# smartstand-usb-dac-i2s-rev-a.net
KiCad netlist of a schematic drawn in EAGLE
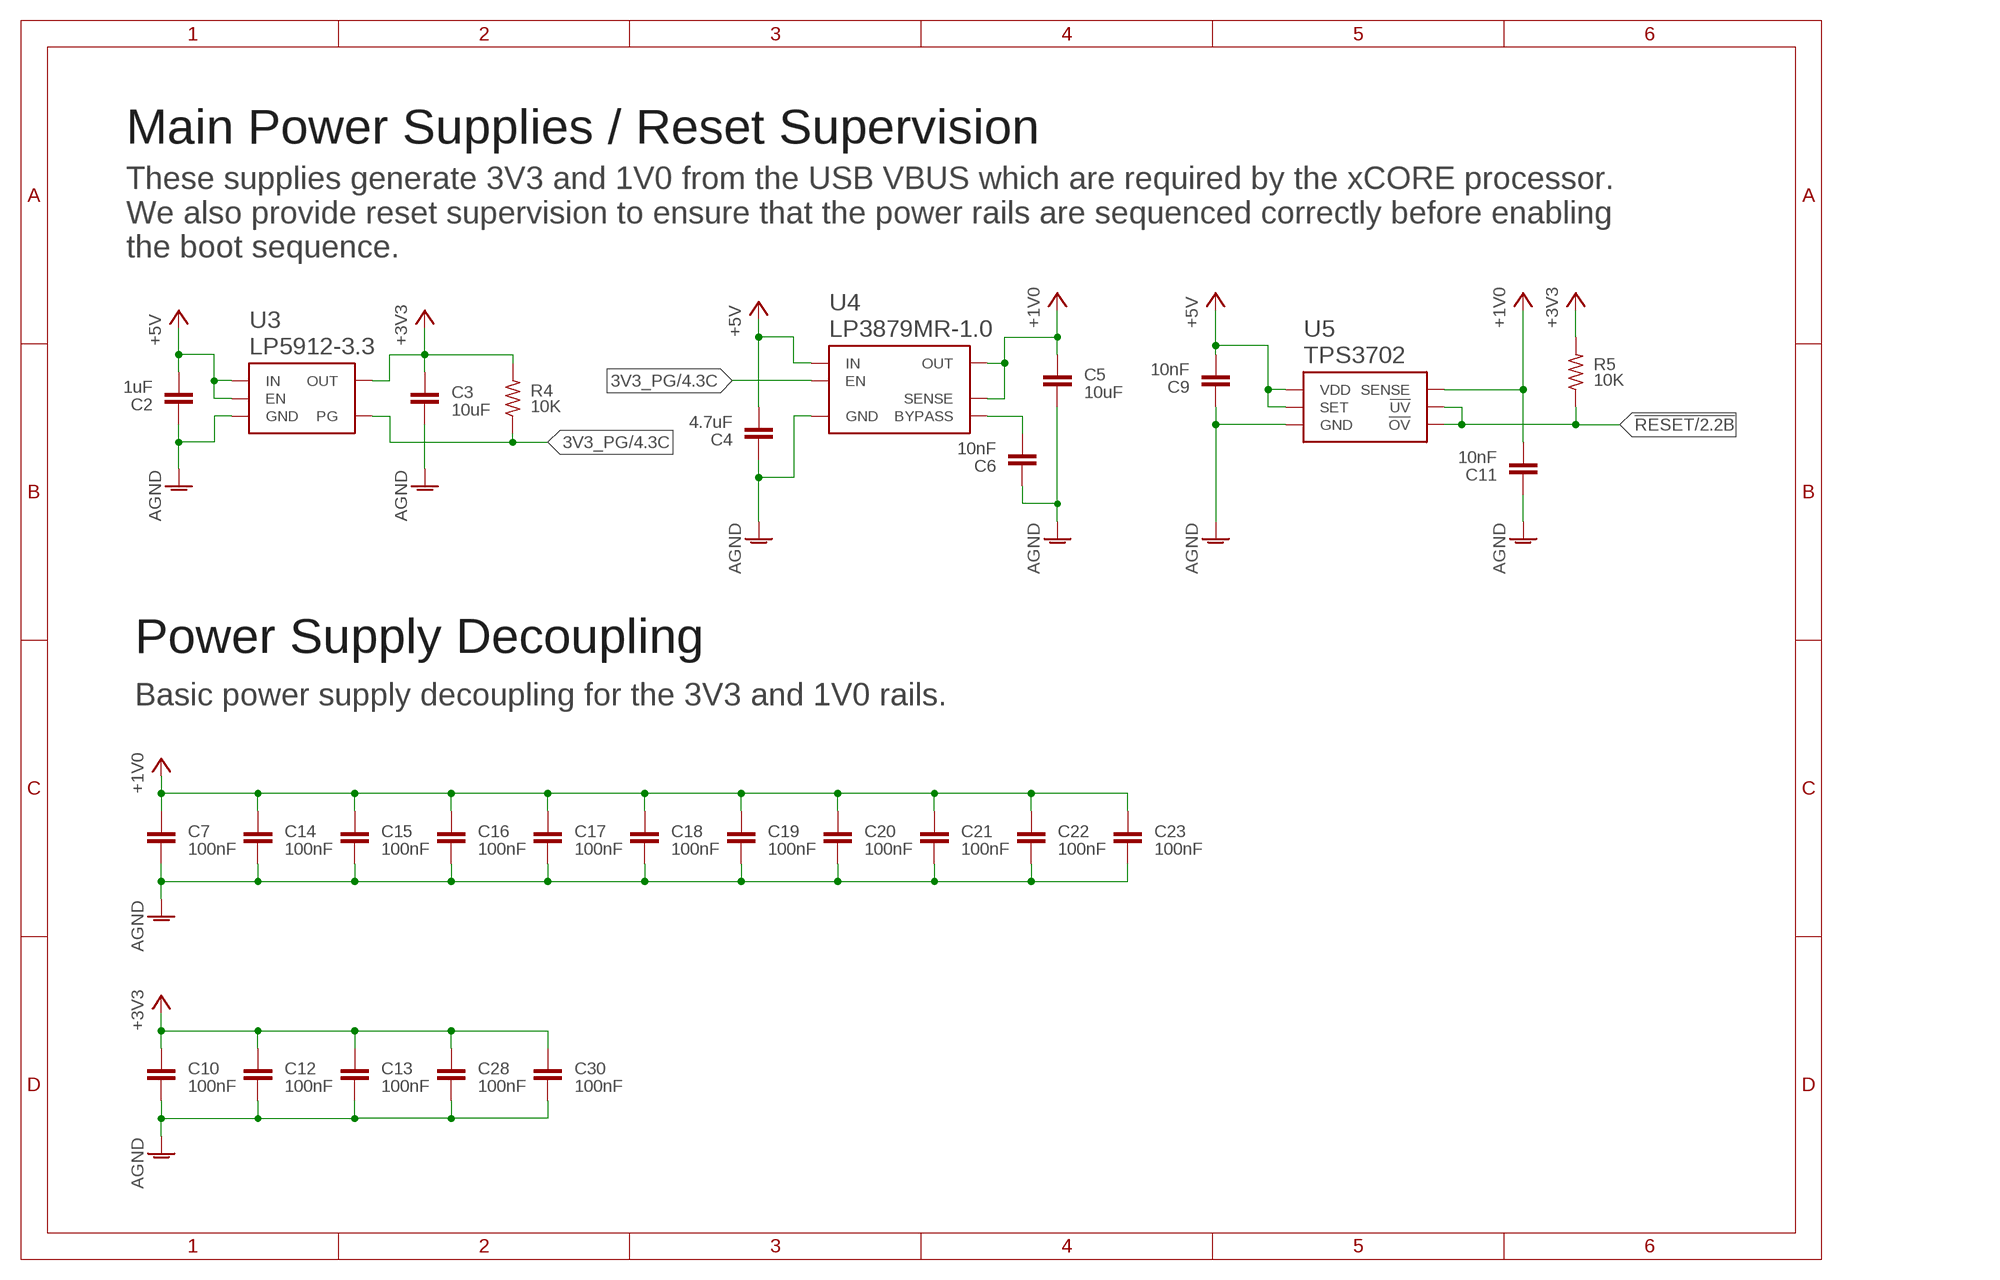
[diagram p0: schematic, sheet 1]
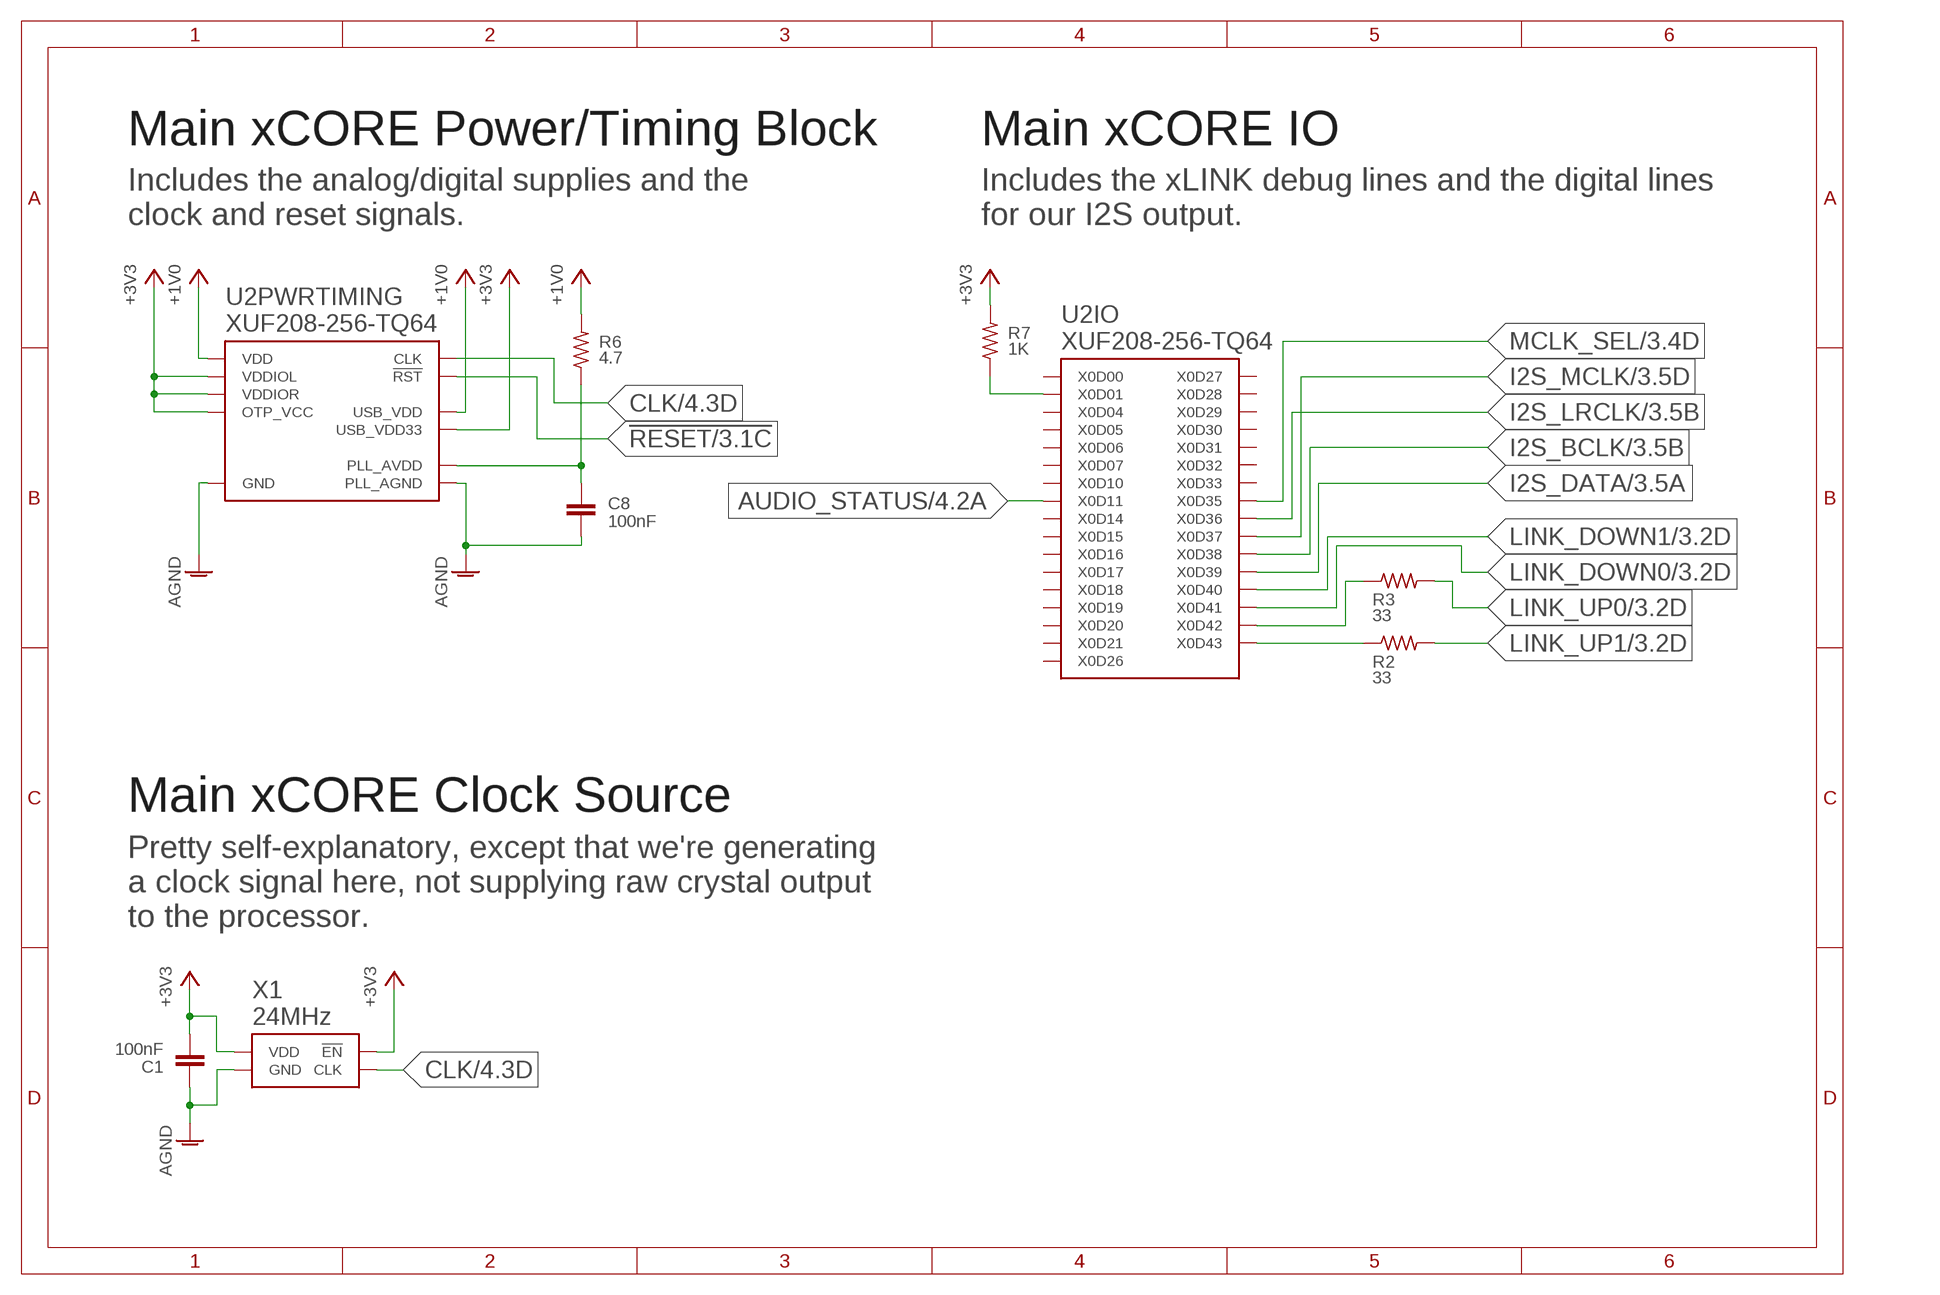
[diagram p1: schematic, sheet 2]
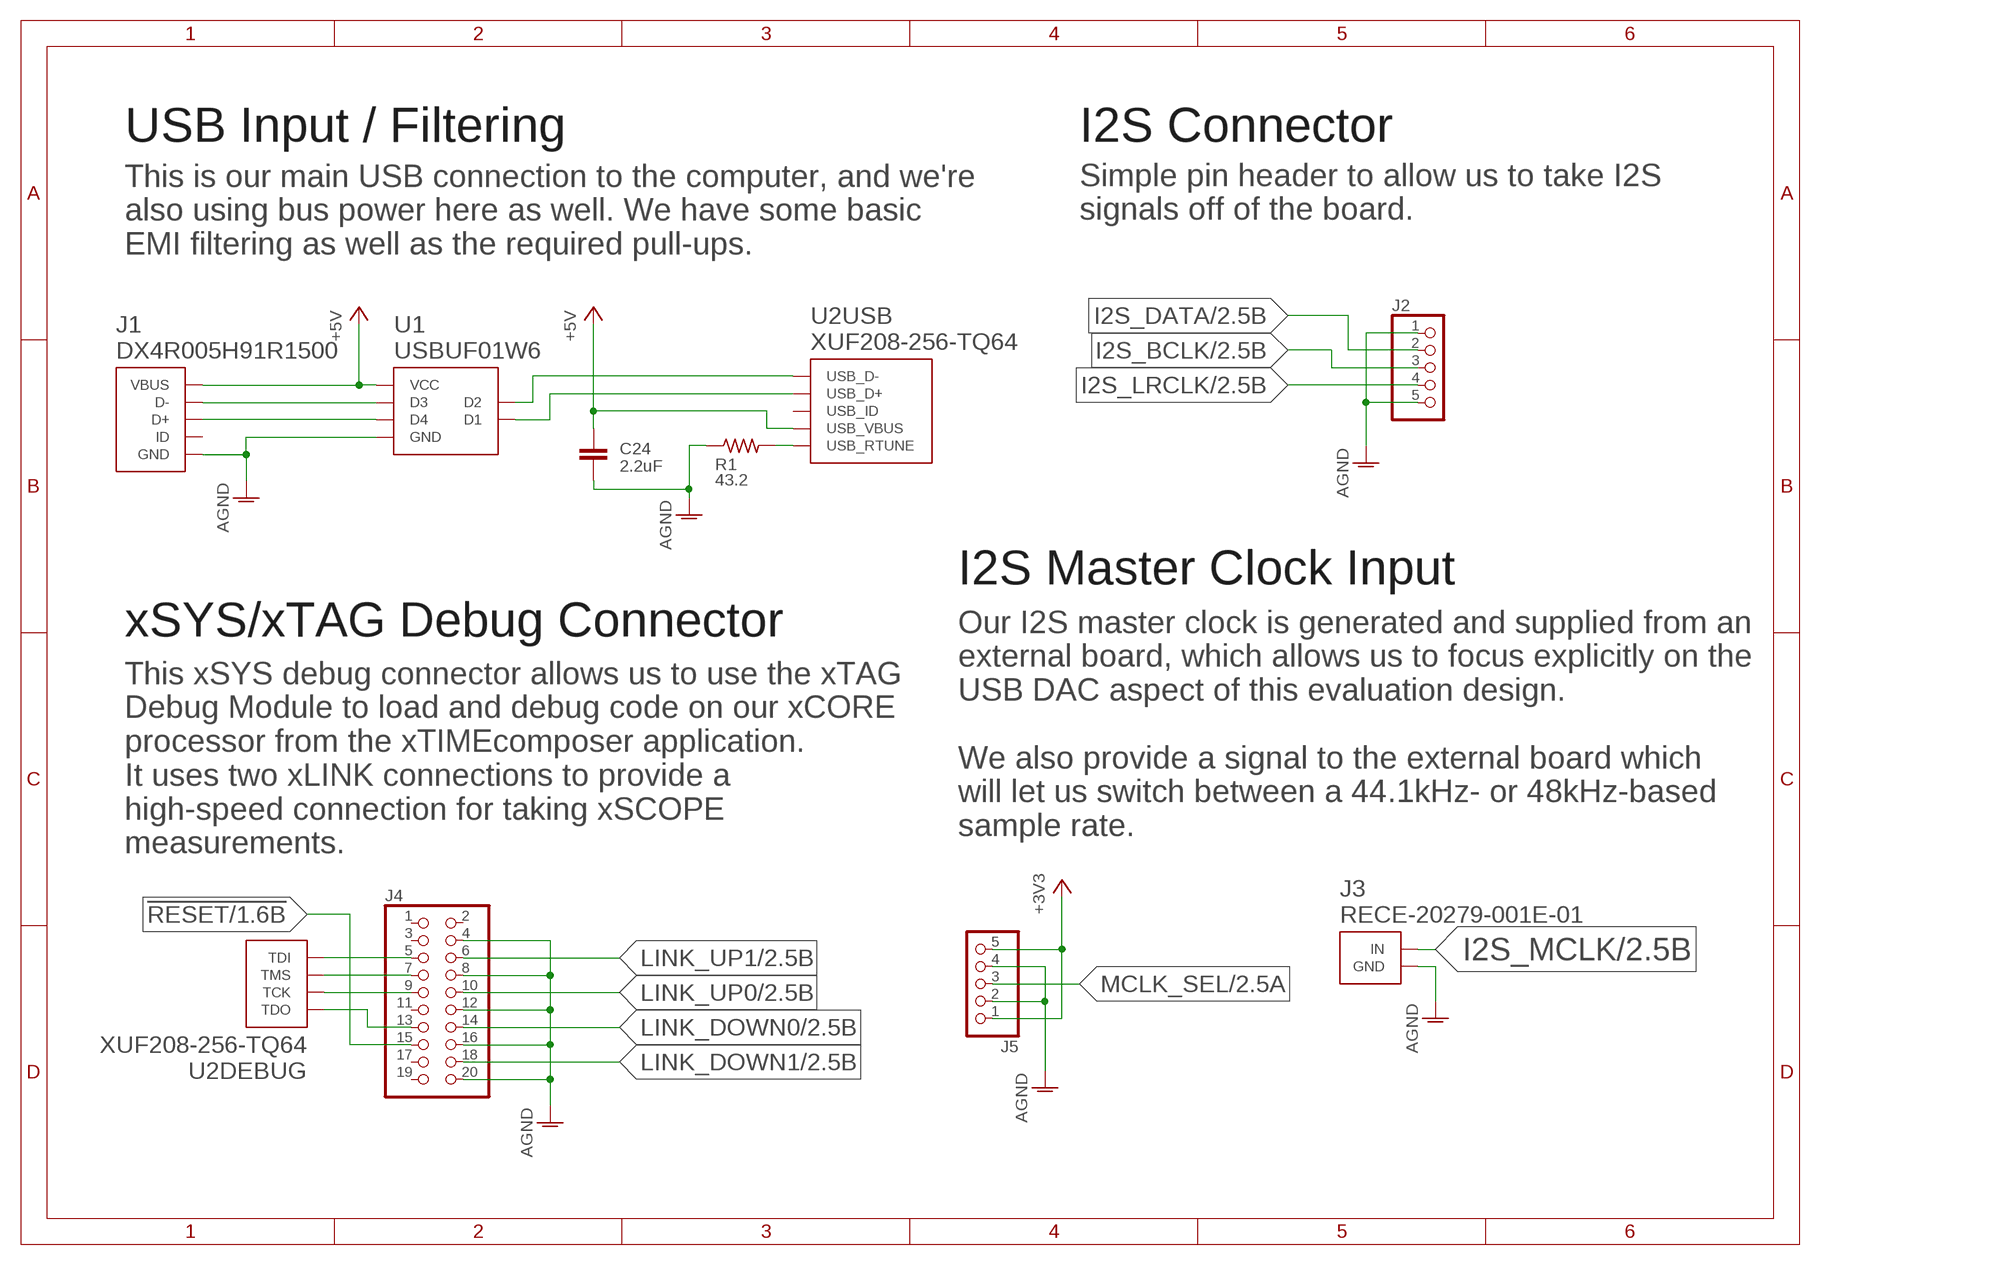
[diagram p2: schematic, sheet 3]
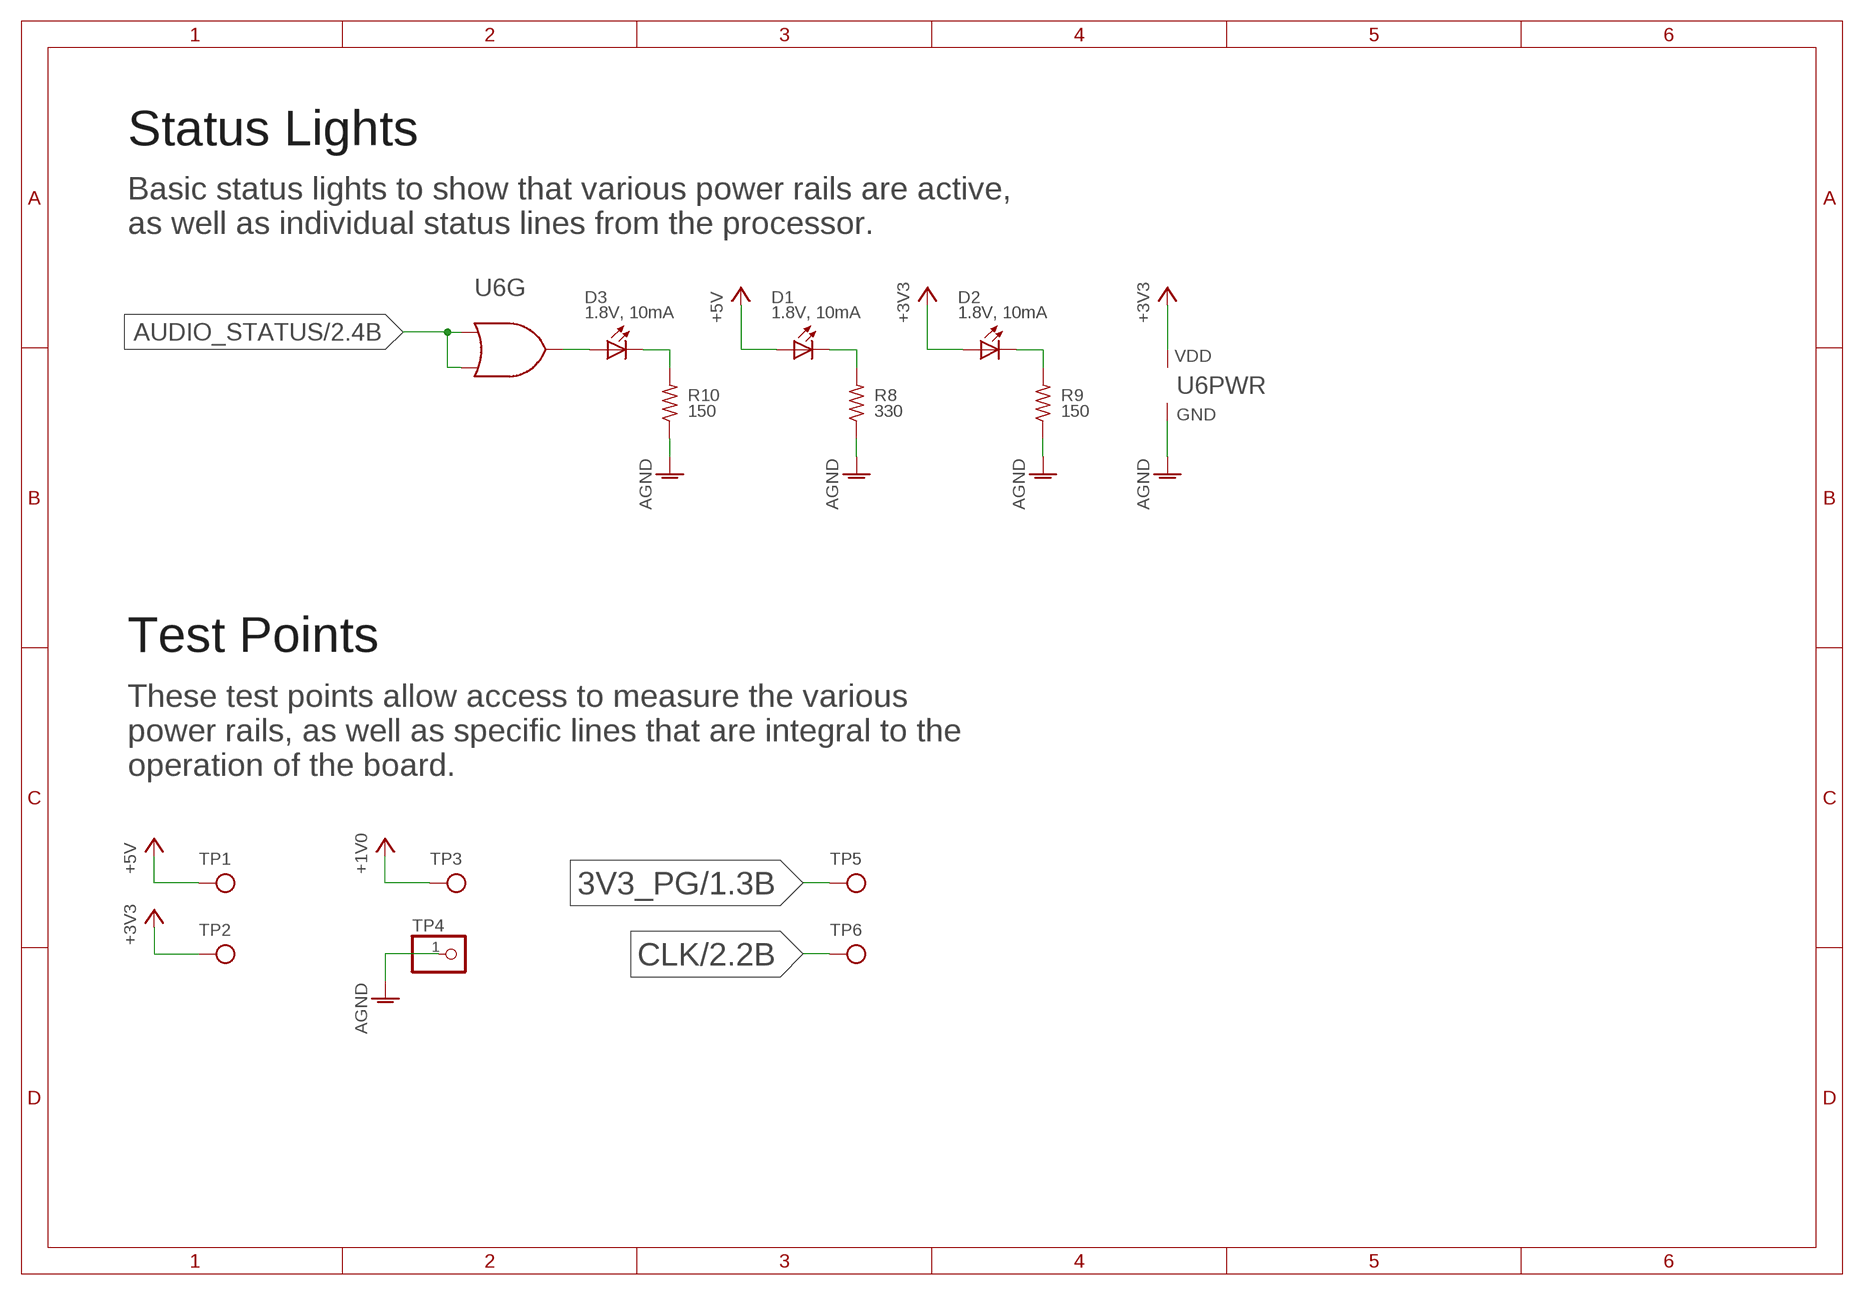
[diagram p3: schematic, sheet 4]

(export (version "E")
  (design (tool "Eeschema 10.0.6"))
  (components
    (comp (ref "D1")
      (value "1.8V, 10mA")
      (footprint "eagle-import:DIALIGHT-0603")
      (libsource (lib "eagle-import") (part "DIALIGHT-598-MICROSMD-0603"))
    )
    (comp (ref "D2")
      (value "1.8V, 10mA")
      (footprint "eagle-import:DIALIGHT-0603")
      (libsource (lib "eagle-import") (part "DIALIGHT-598-MICROSMD-0603"))
    )
    (comp (ref "D3")
      (value "1.8V, 10mA")
      (footprint "eagle-import:DIALIGHT-0603")
      (libsource (lib "eagle-import") (part "DIALIGHT-598-MICROSMD-0603"))
    )
    (comp (ref "R8")
      (value "330")
      (footprint "eagle-import:R0402")
      (libsource (lib "eagle-import") (part "R-US-VERTICALR0402"))
    )
    (comp (ref "R9")
      (value "150")
      (footprint "eagle-import:R0402")
      (libsource (lib "eagle-import") (part "R-US-VERTICALR0402"))
    )
    (comp (ref "R10")
      (value "150")
      (footprint "eagle-import:R0402")
      (libsource (lib "eagle-import") (part "R-US-VERTICALR0402"))
    )
    (comp (ref "TP1")
      (value "TESTPOINT-1.5MM")
      (footprint "eagle-import:TESTPOINT-1.5")
      (libsource (lib "eagle-import") (part "TESTPOINT-1.5MM"))
    )
    (comp (ref "TP2")
      (value "TESTPOINT-1.5MM")
      (footprint "eagle-import:TESTPOINT-1.5")
      (libsource (lib "eagle-import") (part "TESTPOINT-1.5MM"))
    )
    (comp (ref "TP3")
      (value "TESTPOINT-1.5MM")
      (footprint "eagle-import:TESTPOINT-1.5")
      (libsource (lib "eagle-import") (part "TESTPOINT-1.5MM"))
    )
    (comp (ref "TP4")
      (value "PINHD-1X1")
      (footprint "eagle-import:1X01")
      (libsource (lib "eagle-import") (part "PINHD-1X1"))
    )
    (comp (ref "TP5")
      (value "TESTPOINT-1.5MM")
      (footprint "eagle-import:TESTPOINT-1.5")
      (libsource (lib "eagle-import") (part "TESTPOINT-1.5MM"))
    )
    (comp (ref "TP6")
      (value "TESTPOINT-1.5MM")
      (footprint "eagle-import:TESTPOINT-1.5")
      (libsource (lib "eagle-import") (part "TESTPOINT-1.5MM"))
    )
    (comp (ref "U6")
      (value "SN74LVC1G32DRL")
      (footprint "eagle-import:R-PDSO-N5")
      (fields (field (name "PN") "SN74LVC1G32DRLR"))
      (libsource (lib "eagle-import") (part "SN74LVC1G32DRL"))
    )
    (comp (ref "C1")
      (value "100nF")
      (footprint "eagle-import:C0402")
      (libsource (lib "eagle-import") (part "C-EUC0402"))
    )
    (comp (ref "C8")
      (value "100nF")
      (footprint "eagle-import:C0402")
      (libsource (lib "eagle-import") (part "C-EUC0402"))
    )
    (comp (ref "R2")
      (value "33")
      (footprint "eagle-import:R0402")
      (libsource (lib "eagle-import") (part "R-US_R0402"))
    )
    (comp (ref "R3")
      (value "33")
      (footprint "eagle-import:R0402")
      (libsource (lib "eagle-import") (part "R-US_R0402"))
    )
    (comp (ref "R6")
      (value "4.7")
      (footprint "eagle-import:R0402")
      (libsource (lib "eagle-import") (part "R-US-VERTICALR0402"))
    )
    (comp (ref "R7")
      (value "1K")
      (footprint "eagle-import:R0402")
      (libsource (lib "eagle-import") (part "R-US-VERTICALR0402"))
    )
    (comp (ref "U2")
      (value "XUF208-256-TQ64")
      (footprint "eagle-import:TQFP-64-EXPOSED-PAD")
      (fields (field (name "PN") "XUF208-256-TQ64-C10"))
      (libsource (lib "eagle-import") (part "XUF208-256-TQ64"))
    )
    (comp (ref "X1")
      (value "24MHz")
      (footprint "eagle-import:KC2520C")
      (libsource (lib "eagle-import") (part "KC2520C"))
    )
    (comp (ref "C24")
      (value "2.2uF")
      (footprint "eagle-import:C0603")
      (libsource (lib "eagle-import") (part "C-EUC0603"))
    )
    (comp (ref "J1")
      (value "DX4R005H91R1500")
      (footprint "eagle-import:DX4R005H91R1500")
      (libsource (lib "eagle-import") (part "DX4R005H91R1500"))
    )
    (comp (ref "J2")
      (value "PINHD-1X5")
      (footprint "eagle-import:1X05")
      (libsource (lib "eagle-import") (part "PINHD-1X5"))
    )
    (comp (ref "J3")
      (value "RECE-20279-001E-01")
      (footprint "eagle-import:IPEX-MHF")
      (libsource (lib "eagle-import") (part "RECE-20279-001E-01"))
    )
    (comp (ref "J4")
      (value "PINHD-2X10")
      (footprint "eagle-import:2X10")
      (libsource (lib "eagle-import") (part "PINHD-2X10"))
    )
    (comp (ref "J5")
      (value "PINHD-1X5")
      (footprint "eagle-import:1X05")
      (libsource (lib "eagle-import") (part "PINHD-1X5"))
    )
    (comp (ref "R1")
      (value "43.2")
      (footprint "eagle-import:R0402")
      (libsource (lib "eagle-import") (part "R-US_R0402"))
    )
    (comp (ref "U1")
      (value "USBUF01W6")
      (footprint "eagle-import:SOT323-6L")
      (libsource (lib "eagle-import") (part "USBUF"))
    )
    (comp (ref "C2")
      (value "1uF")
      (footprint "eagle-import:C0603")
      (libsource (lib "eagle-import") (part "C-EUC0603"))
    )
    (comp (ref "C3")
      (value "10uF")
      (footprint "eagle-import:C0603")
      (libsource (lib "eagle-import") (part "C-EUC0603"))
    )
    (comp (ref "C4")
      (value "4.7uF")
      (footprint "eagle-import:C0603")
      (libsource (lib "eagle-import") (part "C-EUC0603"))
    )
    (comp (ref "C5")
      (value "10uF")
      (footprint "eagle-import:C0603")
      (libsource (lib "eagle-import") (part "C-EUC0603"))
    )
    (comp (ref "C6")
      (value "10nF")
      (footprint "eagle-import:C0402")
      (libsource (lib "eagle-import") (part "C-EUC0402"))
    )
    (comp (ref "C7")
      (value "100nF")
      (footprint "eagle-import:C0402")
      (libsource (lib "eagle-import") (part "C-EUC0402"))
    )
    (comp (ref "C9")
      (value "10nF")
      (footprint "eagle-import:C0402")
      (libsource (lib "eagle-import") (part "C-EUC0402"))
    )
    (comp (ref "C10")
      (value "100nF")
      (footprint "eagle-import:C0402")
      (libsource (lib "eagle-import") (part "C-EUC0402"))
    )
    (comp (ref "C11")
      (value "10nF")
      (footprint "eagle-import:C0402")
      (libsource (lib "eagle-import") (part "C-EUC0402"))
    )
    (comp (ref "C12")
      (value "100nF")
      (footprint "eagle-import:C0402")
      (libsource (lib "eagle-import") (part "C-EUC0402"))
    )
    (comp (ref "C13")
      (value "100nF")
      (footprint "eagle-import:C0402")
      (libsource (lib "eagle-import") (part "C-EUC0402"))
    )
    (comp (ref "C14")
      (value "100nF")
      (footprint "eagle-import:C0402")
      (libsource (lib "eagle-import") (part "C-EUC0402"))
    )
    (comp (ref "C15")
      (value "100nF")
      (footprint "eagle-import:C0402")
      (libsource (lib "eagle-import") (part "C-EUC0402"))
    )
    (comp (ref "C16")
      (value "100nF")
      (footprint "eagle-import:C0402")
      (libsource (lib "eagle-import") (part "C-EUC0402"))
    )
    (comp (ref "C17")
      (value "100nF")
      (footprint "eagle-import:C0402")
      (libsource (lib "eagle-import") (part "C-EUC0402"))
    )
    (comp (ref "C18")
      (value "100nF")
      (footprint "eagle-import:C0402")
      (libsource (lib "eagle-import") (part "C-EUC0402"))
    )
    (comp (ref "C19")
      (value "100nF")
      (footprint "eagle-import:C0402")
      (libsource (lib "eagle-import") (part "C-EUC0402"))
    )
    (comp (ref "C20")
      (value "100nF")
      (footprint "eagle-import:C0402")
      (libsource (lib "eagle-import") (part "C-EUC0402"))
    )
    (comp (ref "C21")
      (value "100nF")
      (footprint "eagle-import:C0402")
      (libsource (lib "eagle-import") (part "C-EUC0402"))
    )
    (comp (ref "C22")
      (value "100nF")
      (footprint "eagle-import:C0402")
      (libsource (lib "eagle-import") (part "C-EUC0402"))
    )
    (comp (ref "C23")
      (value "100nF")
      (footprint "eagle-import:C0402")
      (libsource (lib "eagle-import") (part "C-EUC0402"))
    )
    (comp (ref "C28")
      (value "100nF")
      (footprint "eagle-import:C0402")
      (libsource (lib "eagle-import") (part "C-EUC0402"))
    )
    (comp (ref "C30")
      (value "100nF")
      (footprint "eagle-import:C0402")
      (libsource (lib "eagle-import") (part "C-EUC0402"))
    )
    (comp (ref "R4")
      (value "10K")
      (footprint "eagle-import:R0402")
      (libsource (lib "eagle-import") (part "R-US-VERTICALR0402"))
    )
    (comp (ref "R5")
      (value "10K")
      (footprint "eagle-import:R0402")
      (libsource (lib "eagle-import") (part "R-US-VERTICALR0402"))
    )
    (comp (ref "U3")
      (value "LP5912-3.3")
      (footprint "eagle-import:P-PWSON-N6")
      (libsource (lib "eagle-import") (part "LP5912-3.3DRV"))
    )
    (comp (ref "U4")
      (value "LP3879MR-1.0")
      (footprint "eagle-import:PSOP-8-POWERPAD-DDA")
      (libsource (lib "eagle-import") (part "LP3879MR-1.0"))
    )
    (comp (ref "U5")
      (value "TPS3702")
      (footprint "eagle-import:R-PDSO-G6")
      (libsource (lib "eagle-import") (part "TPS3702CX10DDC"))
    )
  )
  (nets
    (net (code "1") (name "+1V0") (class "Default")
      (node (ref "C11") (pin "2") (pinfunction "2_2") (pintype "passive"))
      (node (ref "C14") (pin "1") (pinfunction "1_1") (pintype "passive"))
      (node (ref "C15") (pin "1") (pinfunction "1_1") (pintype "passive"))
      (node (ref "C16") (pin "1") (pinfunction "1_1") (pintype "passive"))
      (node (ref "C17") (pin "1") (pinfunction "1_1") (pintype "passive"))
      (node (ref "C18") (pin "1") (pinfunction "1_1") (pintype "passive"))
      (node (ref "C19") (pin "1") (pinfunction "1_1") (pintype "passive"))
      (node (ref "C20") (pin "1") (pinfunction "1_1") (pintype "passive"))
      (node (ref "C21") (pin "1") (pinfunction "1_1") (pintype "passive"))
      (node (ref "C22") (pin "1") (pinfunction "1_1") (pintype "passive"))
      (node (ref "C23") (pin "1") (pinfunction "1_1") (pintype "passive"))
      (node (ref "C5") (pin "1") (pinfunction "1_1") (pintype "passive"))
      (node (ref "C7") (pin "1") (pinfunction "1_1") (pintype "passive"))
      (node (ref "R6") (pin "2") (pinfunction "2_2") (pintype "passive"))
      (node (ref "TP3") (pin "P$1") (pinfunction "P$1_P$1") (pintype "bidirectional"))
      (node (ref "U2") (pin "P$10") (pinfunction "VDD_P$10") (pintype "bidirectional"))
      (node (ref "U2") (pin "P$20") (pinfunction "VDD_P$20") (pintype "bidirectional"))
      (node (ref "U2") (pin "P$27") (pinfunction "USB_VDD_P$27") (pintype "bidirectional"))
      (node (ref "U2") (pin "P$31") (pinfunction "VDD_P$31") (pintype "bidirectional"))
      (node (ref "U2") (pin "P$39") (pinfunction "VDD_P$39") (pintype "bidirectional"))
      (node (ref "U2") (pin "P$40") (pinfunction "VDD_P$40") (pintype "bidirectional"))
      (node (ref "U2") (pin "P$41") (pinfunction "VDD_P$41") (pintype "bidirectional"))
      (node (ref "U2") (pin "P$52") (pinfunction "VDD_P$52") (pintype "bidirectional"))
      (node (ref "U2") (pin "P$56") (pinfunction "VDD_P$56") (pintype "bidirectional"))
      (node (ref "U2") (pin "P$59") (pinfunction "VDD_P$59") (pintype "bidirectional"))
      (node (ref "U2") (pin "P$9") (pinfunction "VDD_P$9") (pintype "bidirectional"))
      (node (ref "U4") (pin "5") (pinfunction "OUT_5") (pintype "passive"))
      (node (ref "U4") (pin "6") (pinfunction "SENSE_6") (pintype "bidirectional"))
      (node (ref "U5") (pin "3") (pinfunction "SENSE_3") (pintype "bidirectional"))
    )
    (net (code "2") (name "+3V3") (class "Default")
      (node (ref "C1") (pin "2") (pinfunction "2_2") (pintype "passive"))
      (node (ref "C10") (pin "1") (pinfunction "1_1") (pintype "passive"))
      (node (ref "C12") (pin "1") (pinfunction "1_1") (pintype "passive"))
      (node (ref "C13") (pin "1") (pinfunction "1_1") (pintype "passive"))
      (node (ref "C28") (pin "1") (pinfunction "1_1") (pintype "passive"))
      (node (ref "C3") (pin "1") (pinfunction "1_1") (pintype "passive"))
      (node (ref "C30") (pin "1") (pinfunction "1_1") (pintype "passive"))
      (node (ref "D2") (pin "1") (pinfunction "A_1") (pintype "passive"))
      (node (ref "J5") (pin "1") (pinfunction "1_1") (pintype "passive"))
      (node (ref "J5") (pin "5") (pinfunction "5_5") (pintype "passive"))
      (node (ref "R4") (pin "2") (pinfunction "2_2") (pintype "passive"))
      (node (ref "R5") (pin "2") (pinfunction "2_2") (pintype "passive"))
      (node (ref "R7") (pin "2") (pinfunction "2_2") (pintype "passive"))
      (node (ref "TP2") (pin "P$1") (pinfunction "P$1_P$1") (pintype "bidirectional"))
      (node (ref "U2") (pin "P$13") (pinfunction "VDDIOL_P$13") (pintype "bidirectional"))
      (node (ref "U2") (pin "P$22") (pinfunction "USB_VDD33_P$22") (pintype "bidirectional"))
      (node (ref "U2") (pin "P$3") (pinfunction "VDDIOL_P$3") (pintype "bidirectional"))
      (node (ref "U2") (pin "P$34") (pinfunction "VDDIOR_P$34") (pintype "bidirectional"))
      (node (ref "U2") (pin "P$44") (pinfunction "VDDIOR_P$44") (pintype "bidirectional"))
      (node (ref "U2") (pin "P$55") (pinfunction "OTP_VCC_P$55") (pintype "bidirectional"))
      (node (ref "U3") (pin "P$1") (pinfunction "OUT_P$1") (pintype "bidirectional"))
      (node (ref "U6") (pin "5") (pinfunction "VDD_5") (pintype "bidirectional"))
      (node (ref "X1") (pin "P$1") (pinfunction "~{EN}_P$1") (pintype "bidirectional"))
      (node (ref "X1") (pin "P$4") (pinfunction "VDD_P$4") (pintype "bidirectional"))
    )
    (net (code "3") (name "+5V") (class "Default")
      (node (ref "C2") (pin "2") (pinfunction "2_2") (pintype "passive"))
      (node (ref "C24") (pin "1") (pinfunction "1_1") (pintype "passive"))
      (node (ref "C4") (pin "2") (pinfunction "2_2") (pintype "passive"))
      (node (ref "C9") (pin "2") (pinfunction "2_2") (pintype "passive"))
      (node (ref "D1") (pin "1") (pinfunction "A_1") (pintype "passive"))
      (node (ref "J1") (pin "P$1") (pinfunction "VBUS_P$1") (pintype "bidirectional"))
      (node (ref "TP1") (pin "P$1") (pinfunction "P$1_P$1") (pintype "bidirectional"))
      (node (ref "U1") (pin "P$5") (pinfunction "VCC_P$5") (pintype "power_in"))
      (node (ref "U2") (pin "P$23") (pinfunction "USB_VBUS_P$23") (pintype "bidirectional"))
      (node (ref "U3") (pin "P$4") (pinfunction "EN_P$4") (pintype "bidirectional"))
      (node (ref "U3") (pin "P$6") (pinfunction "IN_P$6") (pintype "bidirectional"))
      (node (ref "U4") (pin "4") (pinfunction "IN_4") (pintype "power_in"))
      (node (ref "U5") (pin "4") (pinfunction "SET_4") (pintype "bidirectional"))
      (node (ref "U5") (pin "5") (pinfunction "VDD_5") (pintype "bidirectional"))
    )
    (net (code "4") (name "3V3_PG") (class "Default")
      (node (ref "R4") (pin "1") (pinfunction "1_1") (pintype "passive"))
      (node (ref "TP5") (pin "P$1") (pinfunction "P$1_P$1") (pintype "bidirectional"))
      (node (ref "U3") (pin "P$3") (pinfunction "PG_P$3") (pintype "bidirectional"))
      (node (ref "U4") (pin "8") (pinfunction "EN_8") (pintype "bidirectional"))
    )
    (net (code "5") (name "AGND") (class "Default")
      (node (ref "C1") (pin "1") (pinfunction "1_1") (pintype "passive"))
      (node (ref "C10") (pin "2") (pinfunction "2_2") (pintype "passive"))
      (node (ref "C11") (pin "1") (pinfunction "1_1") (pintype "passive"))
      (node (ref "C12") (pin "2") (pinfunction "2_2") (pintype "passive"))
      (node (ref "C13") (pin "2") (pinfunction "2_2") (pintype "passive"))
      (node (ref "C14") (pin "2") (pinfunction "2_2") (pintype "passive"))
      (node (ref "C15") (pin "2") (pinfunction "2_2") (pintype "passive"))
      (node (ref "C16") (pin "2") (pinfunction "2_2") (pintype "passive"))
      (node (ref "C17") (pin "2") (pinfunction "2_2") (pintype "passive"))
      (node (ref "C18") (pin "2") (pinfunction "2_2") (pintype "passive"))
      (node (ref "C19") (pin "2") (pinfunction "2_2") (pintype "passive"))
      (node (ref "C2") (pin "1") (pinfunction "1_1") (pintype "passive"))
      (node (ref "C20") (pin "2") (pinfunction "2_2") (pintype "passive"))
      (node (ref "C21") (pin "2") (pinfunction "2_2") (pintype "passive"))
      (node (ref "C22") (pin "2") (pinfunction "2_2") (pintype "passive"))
      (node (ref "C23") (pin "2") (pinfunction "2_2") (pintype "passive"))
      (node (ref "C24") (pin "2") (pinfunction "2_2") (pintype "passive"))
      (node (ref "C28") (pin "2") (pinfunction "2_2") (pintype "passive"))
      (node (ref "C3") (pin "2") (pinfunction "2_2") (pintype "passive"))
      (node (ref "C30") (pin "2") (pinfunction "2_2") (pintype "passive"))
      (node (ref "C4") (pin "1") (pinfunction "1_1") (pintype "passive"))
      (node (ref "C5") (pin "2") (pinfunction "2_2") (pintype "passive"))
      (node (ref "C6") (pin "1") (pinfunction "1_1") (pintype "passive"))
      (node (ref "C7") (pin "2") (pinfunction "2_2") (pintype "passive"))
      (node (ref "C8") (pin "2") (pinfunction "2_2") (pintype "passive"))
      (node (ref "C9") (pin "1") (pinfunction "1_1") (pintype "passive"))
      (node (ref "J1") (pin "P$5") (pinfunction "GND_P$5") (pintype "bidirectional"))
      (node (ref "J2") (pin "1") (pinfunction "1_1") (pintype "passive"))
      (node (ref "J2") (pin "5") (pinfunction "5_5") (pintype "passive"))
      (node (ref "J3") (pin "P$1") (pinfunction "GND_P$1") (pintype "bidirectional"))
      (node (ref "J3") (pin "P$2") (pinfunction "GND_P$2") (pintype "bidirectional"))
      (node (ref "J4") (pin "12") (pinfunction "12_12") (pintype "passive"))
      (node (ref "J4") (pin "16") (pinfunction "16_16") (pintype "passive"))
      (node (ref "J4") (pin "20") (pinfunction "20_20") (pintype "passive"))
      (node (ref "J4") (pin "4") (pinfunction "4_4") (pintype "passive"))
      (node (ref "J4") (pin "8") (pinfunction "8_8") (pintype "passive"))
      (node (ref "J5") (pin "2") (pinfunction "2_2") (pintype "passive"))
      (node (ref "J5") (pin "4") (pinfunction "4_4") (pintype "passive"))
      (node (ref "R1") (pin "1") (pinfunction "1_1") (pintype "passive"))
      (node (ref "R10") (pin "1") (pinfunction "1_1") (pintype "passive"))
      (node (ref "R8") (pin "1") (pinfunction "1_1") (pintype "passive"))
      (node (ref "R9") (pin "1") (pinfunction "1_1") (pintype "passive"))
      (node (ref "TP4") (pin "1") (pinfunction "1_1") (pintype "passive"))
      (node (ref "U1") (pin "P$2") (pinfunction "GND_P$2") (pintype "power_in"))
      (node (ref "U2") (pin "P$54") (pinfunction "PLL_AGND_P$54") (pintype "bidirectional"))
      (node (ref "U2") (pin "P$65") (pinfunction "GND_P$65") (pintype "bidirectional"))
      (node (ref "U2") (pin "P$66") (pinfunction "GND_P$66") (pintype "bidirectional"))
      (node (ref "U2") (pin "P$67") (pinfunction "GND_P$67") (pintype "bidirectional"))
      (node (ref "U2") (pin "P$68") (pinfunction "GND_P$68") (pintype "bidirectional"))
      (node (ref "U2") (pin "P$69") (pinfunction "GND_P$69") (pintype "bidirectional"))
      (node (ref "U2") (pin "P$70") (pinfunction "GND_P$70") (pintype "bidirectional"))
      (node (ref "U2") (pin "P$71") (pinfunction "GND_P$71") (pintype "bidirectional"))
      (node (ref "U2") (pin "P$72") (pinfunction "GND_P$72") (pintype "bidirectional"))
      (node (ref "U2") (pin "P$73") (pinfunction "GND_P$73") (pintype "bidirectional"))
      (node (ref "U2") (pin "P$74") (pinfunction "GND_P$74") (pintype "bidirectional"))
      (node (ref "U3") (pin "P$5") (pinfunction "GND_P$5") (pintype "bidirectional"))
      (node (ref "U3") (pin "P$8") (pinfunction "GND_P$8") (pintype "bidirectional"))
      (node (ref "U3") (pin "P$9") (pinfunction "GND_P$9") (pintype "bidirectional"))
      (node (ref "U3") (pin "P$EP") (pinfunction "GND_P$EP") (pintype "bidirectional"))
      (node (ref "U4") (pin "3") (pinfunction "GND_3") (pintype "power_in"))
      (node (ref "U4") (pin "EP") (pinfunction "GND_EP") (pintype "power_in"))
      (node (ref "U4") (pin "P$1") (pinfunction "GND_P$1") (pintype "power_in"))
      (node (ref "U4") (pin "P$2") (pinfunction "GND_P$2") (pintype "power_in"))
      (node (ref "U4") (pin "P$3") (pinfunction "GND_P$3") (pintype "power_in"))
      (node (ref "U4") (pin "P$4") (pinfunction "GND_P$4") (pintype "power_in"))
      (node (ref "U4") (pin "P$5") (pinfunction "GND_P$5") (pintype "power_in"))
      (node (ref "U4") (pin "P$6") (pinfunction "GND_P$6") (pintype "power_in"))
      (node (ref "U5") (pin "2") (pinfunction "GND_2") (pintype "bidirectional"))
      (node (ref "U6") (pin "3") (pinfunction "GND_3") (pintype "bidirectional"))
      (node (ref "X1") (pin "P$2") (pinfunction "GND_P$2") (pintype "bidirectional"))
    )
    (net (code "6") (name "AUDIO_STATUS") (class "Default")
      (node (ref "U2") (pin "P$16") (pinfunction "X0D11_P$16") (pintype "bidirectional"))
      (node (ref "U6") (pin "1") (pinfunction "A_1") (pintype "input"))
      (node (ref "U6") (pin "2") (pinfunction "B_2") (pintype "input"))
    )
    (net (code "7") (name "CLK") (class "Default")
      (node (ref "TP6") (pin "P$1") (pinfunction "P$1_P$1") (pintype "bidirectional"))
      (node (ref "U2") (pin "P$58") (pinfunction "CLK_P$58") (pintype "bidirectional"))
      (node (ref "X1") (pin "P$3") (pinfunction "CLK_P$3") (pintype "bidirectional"))
    )
    (net (code "8") (name "I2S_BCLK") (class "Default")
      (node (ref "J2") (pin "3") (pinfunction "3_3") (pintype "passive"))
      (node (ref "U2") (pin "P$2") (pinfunction "X0D38_P$2") (pintype "bidirectional"))
    )
    (net (code "9") (name "I2S_DATA") (class "Default")
      (node (ref "J2") (pin "2") (pinfunction "2_2") (pintype "passive"))
      (node (ref "U2") (pin "P$4") (pinfunction "X0D39_P$4") (pintype "bidirectional"))
    )
    (net (code "10") (name "I2S_LRCLK") (class "Default")
      (node (ref "J2") (pin "4") (pinfunction "4_4") (pintype "passive"))
      (node (ref "U2") (pin "P$1") (pinfunction "X0D36_P$1") (pintype "bidirectional"))
    )
    (net (code "11") (name "I2S_MCLK") (class "Default")
      (node (ref "J3") (pin "P$3") (pinfunction "IN_P$3") (pintype "bidirectional"))
      (node (ref "U2") (pin "P$64") (pinfunction "X0D37_P$64") (pintype "bidirectional"))
    )
    (net (code "12") (name "LINK_DOWN0") (class "Default")
      (node (ref "J4") (pin "14") (pinfunction "14_14") (pintype "passive"))
      (node (ref "U2") (pin "P$6") (pinfunction "X0D41_P$6") (pintype "bidirectional"))
    )
    (net (code "13") (name "LINK_DOWN1") (class "Default")
      (node (ref "J4") (pin "18") (pinfunction "18_18") (pintype "passive"))
      (node (ref "U2") (pin "P$5") (pinfunction "X0D40_P$5") (pintype "bidirectional"))
    )
    (net (code "14") (name "LINK_UP0") (class "Default")
      (node (ref "J4") (pin "10") (pinfunction "10_10") (pintype "passive"))
      (node (ref "R3") (pin "2") (pinfunction "2_2") (pintype "passive"))
    )
    (net (code "15") (name "LINK_UP1") (class "Default")
      (node (ref "J4") (pin "6") (pinfunction "6_6") (pintype "passive"))
      (node (ref "R2") (pin "2") (pinfunction "2_2") (pintype "passive"))
    )
    (net (code "16") (name "MCLK_SEL") (class "Default")
      (node (ref "J5") (pin "3") (pinfunction "3_3") (pintype "passive"))
      (node (ref "U2") (pin "P$42") (pinfunction "X0D35_P$42") (pintype "bidirectional"))
    )
    (net (code "17") (name "Net-(D1-C)") (class "Default")
      (node (ref "D1") (pin "2") (pinfunction "C_2") (pintype "passive"))
      (node (ref "R8") (pin "2") (pinfunction "2_2") (pintype "passive"))
    )
    (net (code "18") (name "Net-(D2-C)") (class "Default")
      (node (ref "D2") (pin "2") (pinfunction "C_2") (pintype "passive"))
      (node (ref "R9") (pin "2") (pinfunction "2_2") (pintype "passive"))
    )
    (net (code "19") (name "Net-(D3-A)") (class "Default")
      (node (ref "D3") (pin "1") (pinfunction "A_1") (pintype "passive"))
      (node (ref "U6") (pin "4") (pinfunction "Q_4") (pintype "output"))
    )
    (net (code "20") (name "Net-(D3-C)") (class "Default")
      (node (ref "D3") (pin "2") (pinfunction "C_2") (pintype "passive"))
      (node (ref "R10") (pin "2") (pinfunction "2_2") (pintype "passive"))
    )
    (net (code "21") (name "Net-(J1-D+)") (class "Default")
      (node (ref "J1") (pin "P$3") (pinfunction "D+_P$3") (pintype "bidirectional"))
      (node (ref "U1") (pin "P$6") (pinfunction "D4_P$6") (pintype "input"))
    )
    (net (code "22") (name "Net-(J1-D-)") (class "Default")
      (node (ref "J1") (pin "P$2") (pinfunction "D-_P$2") (pintype "bidirectional"))
      (node (ref "U1") (pin "P$4") (pinfunction "D3_P$4") (pintype "input"))
    )
    (net (code "23") (name "Net-(U1-D1)") (class "Default")
      (node (ref "U1") (pin "P$1") (pinfunction "D1_P$1") (pintype "output"))
      (node (ref "U2") (pin "P$25") (pinfunction "USB_D+_P$25") (pintype "bidirectional"))
    )
    (net (code "24") (name "Net-(U1-D2)") (class "Default")
      (node (ref "U1") (pin "P$3") (pinfunction "D2_P$3") (pintype "output"))
      (node (ref "U2") (pin "P$26") (pinfunction "USB_D-_P$26") (pintype "bidirectional"))
    )
    (net (code "25") (name "Net-(U2A-TCK)") (class "Default")
      (node (ref "J4") (pin "9") (pinfunction "9_9") (pintype "passive"))
      (node (ref "U2") (pin "P$61") (pinfunction "TCK_P$61") (pintype "bidirectional"))
    )
    (net (code "26") (name "Net-(U2A-TDI)") (class "Default")
      (node (ref "J4") (pin "5") (pinfunction "5_5") (pintype "passive"))
      (node (ref "U2") (pin "P$62") (pinfunction "TDI_P$62") (pintype "bidirectional"))
    )
    (net (code "27") (name "Net-(U2A-TDO)") (class "Default")
      (node (ref "J4") (pin "13") (pinfunction "13_13") (pintype "passive"))
      (node (ref "U2") (pin "P$63") (pinfunction "TDO_P$63") (pintype "bidirectional"))
    )
    (net (code "28") (name "Net-(U2A-TMS)") (class "Default")
      (node (ref "J4") (pin "7") (pinfunction "7_7") (pintype "passive"))
      (node (ref "U2") (pin "P$60") (pinfunction "TMS_P$60") (pintype "bidirectional"))
    )
    (net (code "29") (name "Net-(U2B-X0D01)") (class "Default")
      (node (ref "R7") (pin "1") (pinfunction "1_1") (pintype "passive"))
      (node (ref "U2") (pin "P$11") (pinfunction "X0D01_P$11") (pintype "bidirectional"))
    )
    (net (code "30") (name "Net-(U2B-X0D42)") (class "Default")
      (node (ref "R3") (pin "1") (pinfunction "1_1") (pintype "passive"))
      (node (ref "U2") (pin "P$7") (pinfunction "X0D42_P$7") (pintype "bidirectional"))
    )
    (net (code "31") (name "Net-(U2B-X0D43)") (class "Default")
      (node (ref "R2") (pin "1") (pinfunction "1_1") (pintype "passive"))
      (node (ref "U2") (pin "P$8") (pinfunction "X0D43_P$8") (pintype "bidirectional"))
    )
    (net (code "32") (name "Net-(U2C-PLL_AVDD)") (class "Default")
      (node (ref "C8") (pin "1") (pinfunction "1_1") (pintype "passive"))
      (node (ref "R6") (pin "1") (pinfunction "1_1") (pintype "passive"))
      (node (ref "U2") (pin "P$53") (pinfunction "PLL_AVDD_P$53") (pintype "bidirectional"))
    )
    (net (code "33") (name "Net-(U2D-USB_RTUNE)") (class "Default")
      (node (ref "R1") (pin "2") (pinfunction "2_2") (pintype "passive"))
      (node (ref "U2") (pin "P$24") (pinfunction "USB_RTUNE_P$24") (pintype "bidirectional"))
    )
    (net (code "34") (name "Net-(U4-BYPASS)") (class "Default")
      (node (ref "C6") (pin "2") (pinfunction "2_2") (pintype "passive"))
      (node (ref "U4") (pin "1") (pinfunction "BYPASS_1") (pintype "bidirectional"))
    )
    (net (code "35") (name "unconnected-(J1-ID-PadP$4)") (class "Default")
      (node (ref "J1") (pin "P$4") (pinfunction "ID_P$4") (pintype "bidirectional"))
    )
    (net (code "36") (name "unconnected-(J4-Pad1)") (class "Default")
      (node (ref "J4") (pin "1") (pinfunction "1_1") (pintype "passive"))
    )
    (net (code "37") (name "unconnected-(J4-Pad2)") (class "Default")
      (node (ref "J4") (pin "2") (pinfunction "2_2") (pintype "passive"))
    )
    (net (code "38") (name "unconnected-(J4-Pad3)") (class "Default")
      (node (ref "J4") (pin "3") (pinfunction "3_3") (pintype "passive"))
    )
    (net (code "39") (name "unconnected-(J4-Pad11)") (class "Default")
      (node (ref "J4") (pin "11") (pinfunction "11_11") (pintype "passive"))
    )
    (net (code "40") (name "unconnected-(J4-Pad17)") (class "Default")
      (node (ref "J4") (pin "17") (pinfunction "17_17") (pintype "passive"))
    )
    (net (code "41") (name "unconnected-(J4-Pad19)") (class "Default")
      (node (ref "J4") (pin "19") (pinfunction "19_19") (pintype "passive"))
    )
    (net (code "42") (name "unconnected-(U2B-X0D00-PadP$14)") (class "Default")
      (node (ref "U2") (pin "P$14") (pinfunction "X0D00_P$14") (pintype "bidirectional"))
    )
    (net (code "43") (name "unconnected-(U2B-X0D04-PadP$15)") (class "Default")
      (node (ref "U2") (pin "P$15") (pinfunction "X0D04_P$15") (pintype "bidirectional"))
    )
    (net (code "44") (name "unconnected-(U2B-X0D05-PadP$17)") (class "Default")
      (node (ref "U2") (pin "P$17") (pinfunction "X0D05_P$17") (pintype "bidirectional"))
    )
    (net (code "45") (name "unconnected-(U2B-X0D06-PadP$18)") (class "Default")
      (node (ref "U2") (pin "P$18") (pinfunction "X0D06_P$18") (pintype "bidirectional"))
    )
    (net (code "46") (name "unconnected-(U2B-X0D07-PadP$19)") (class "Default")
      (node (ref "U2") (pin "P$19") (pinfunction "X0D07_P$19") (pintype "bidirectional"))
    )
    (net (code "47") (name "unconnected-(U2B-X0D10-PadP$12)") (class "Default")
      (node (ref "U2") (pin "P$12") (pinfunction "X0D10_P$12") (pintype "bidirectional"))
    )
    (net (code "48") (name "unconnected-(U2B-X0D14-PadP$28)") (class "Default")
      (node (ref "U2") (pin "P$28") (pinfunction "X0D14_P$28") (pintype "bidirectional"))
    )
    (net (code "49") (name "unconnected-(U2B-X0D15-PadP$29)") (class "Default")
      (node (ref "U2") (pin "P$29") (pinfunction "X0D15_P$29") (pintype "bidirectional"))
    )
    (net (code "50") (name "unconnected-(U2B-X0D16-PadP$35)") (class "Default")
      (node (ref "U2") (pin "P$35") (pinfunction "X0D16_P$35") (pintype "bidirectional"))
    )
    (net (code "51") (name "unconnected-(U2B-X0D17-PadP$36)") (class "Default")
      (node (ref "U2") (pin "P$36") (pinfunction "X0D17_P$36") (pintype "bidirectional"))
    )
    (net (code "52") (name "unconnected-(U2B-X0D18-PadP$37)") (class "Default")
      (node (ref "U2") (pin "P$37") (pinfunction "X0D18_P$37") (pintype "bidirectional"))
    )
    (net (code "53") (name "unconnected-(U2B-X0D19-PadP$38)") (class "Default")
      (node (ref "U2") (pin "P$38") (pinfunction "X0D19_P$38") (pintype "bidirectional"))
    )
    (net (code "54") (name "unconnected-(U2B-X0D20-PadP$30)") (class "Default")
      (node (ref "U2") (pin "P$30") (pinfunction "X0D20_P$30") (pintype "bidirectional"))
    )
    (net (code "55") (name "unconnected-(U2B-X0D21-PadP$32)") (class "Default")
      (node (ref "U2") (pin "P$32") (pinfunction "X0D21_P$32") (pintype "bidirectional"))
    )
    (net (code "56") (name "unconnected-(U2B-X0D26-PadP$43)") (class "Default")
      (node (ref "U2") (pin "P$43") (pinfunction "X0D26_P$43") (pintype "bidirectional"))
    )
    (net (code "57") (name "unconnected-(U2B-X0D27-PadP$45)") (class "Default")
      (node (ref "U2") (pin "P$45") (pinfunction "X0D27_P$45") (pintype "bidirectional"))
    )
    (net (code "58") (name "unconnected-(U2B-X0D28-PadP$47)") (class "Default")
      (node (ref "U2") (pin "P$47") (pinfunction "X0D28_P$47") (pintype "bidirectional"))
    )
    (net (code "59") (name "unconnected-(U2B-X0D29-PadP$49)") (class "Default")
      (node (ref "U2") (pin "P$49") (pinfunction "X0D29_P$49") (pintype "bidirectional"))
    )
    (net (code "60") (name "unconnected-(U2B-X0D30-PadP$50)") (class "Default")
      (node (ref "U2") (pin "P$50") (pinfunction "X0D30_P$50") (pintype "bidirectional"))
    )
    (net (code "61") (name "unconnected-(U2B-X0D31-PadP$51)") (class "Default")
      (node (ref "U2") (pin "P$51") (pinfunction "X0D31_P$51") (pintype "bidirectional"))
    )
    (net (code "62") (name "unconnected-(U2B-X0D32-PadP$46)") (class "Default")
      (node (ref "U2") (pin "P$46") (pinfunction "X0D32_P$46") (pintype "bidirectional"))
    )
    (net (code "63") (name "unconnected-(U2B-X0D33-PadP$48)") (class "Default")
      (node (ref "U2") (pin "P$48") (pinfunction "X0D33_P$48") (pintype "bidirectional"))
    )
    (net (code "64") (name "unconnected-(U2D-USB_ID-PadP$21)") (class "Default")
      (node (ref "U2") (pin "P$21") (pinfunction "USB_ID_P$21") (pintype "bidirectional"))
    )
    (net (code "65") (name "~{RESET}") (class "Default")
      (node (ref "J4") (pin "15") (pinfunction "15_15") (pintype "passive"))
      (node (ref "R5") (pin "1") (pinfunction "1_1") (pintype "passive"))
      (node (ref "U2") (pin "P$57") (pinfunction "~{RST}_P$57") (pintype "bidirectional"))
      (node (ref "U5") (pin "1") (pinfunction "~{UV}_1") (pintype "bidirectional"))
      (node (ref "U5") (pin "6") (pinfunction "~{OV}_6") (pintype "bidirectional"))
    )
  )
)
